# easyeda.net
KiCad netlist of a schematic drawn in EasyEDA Pro
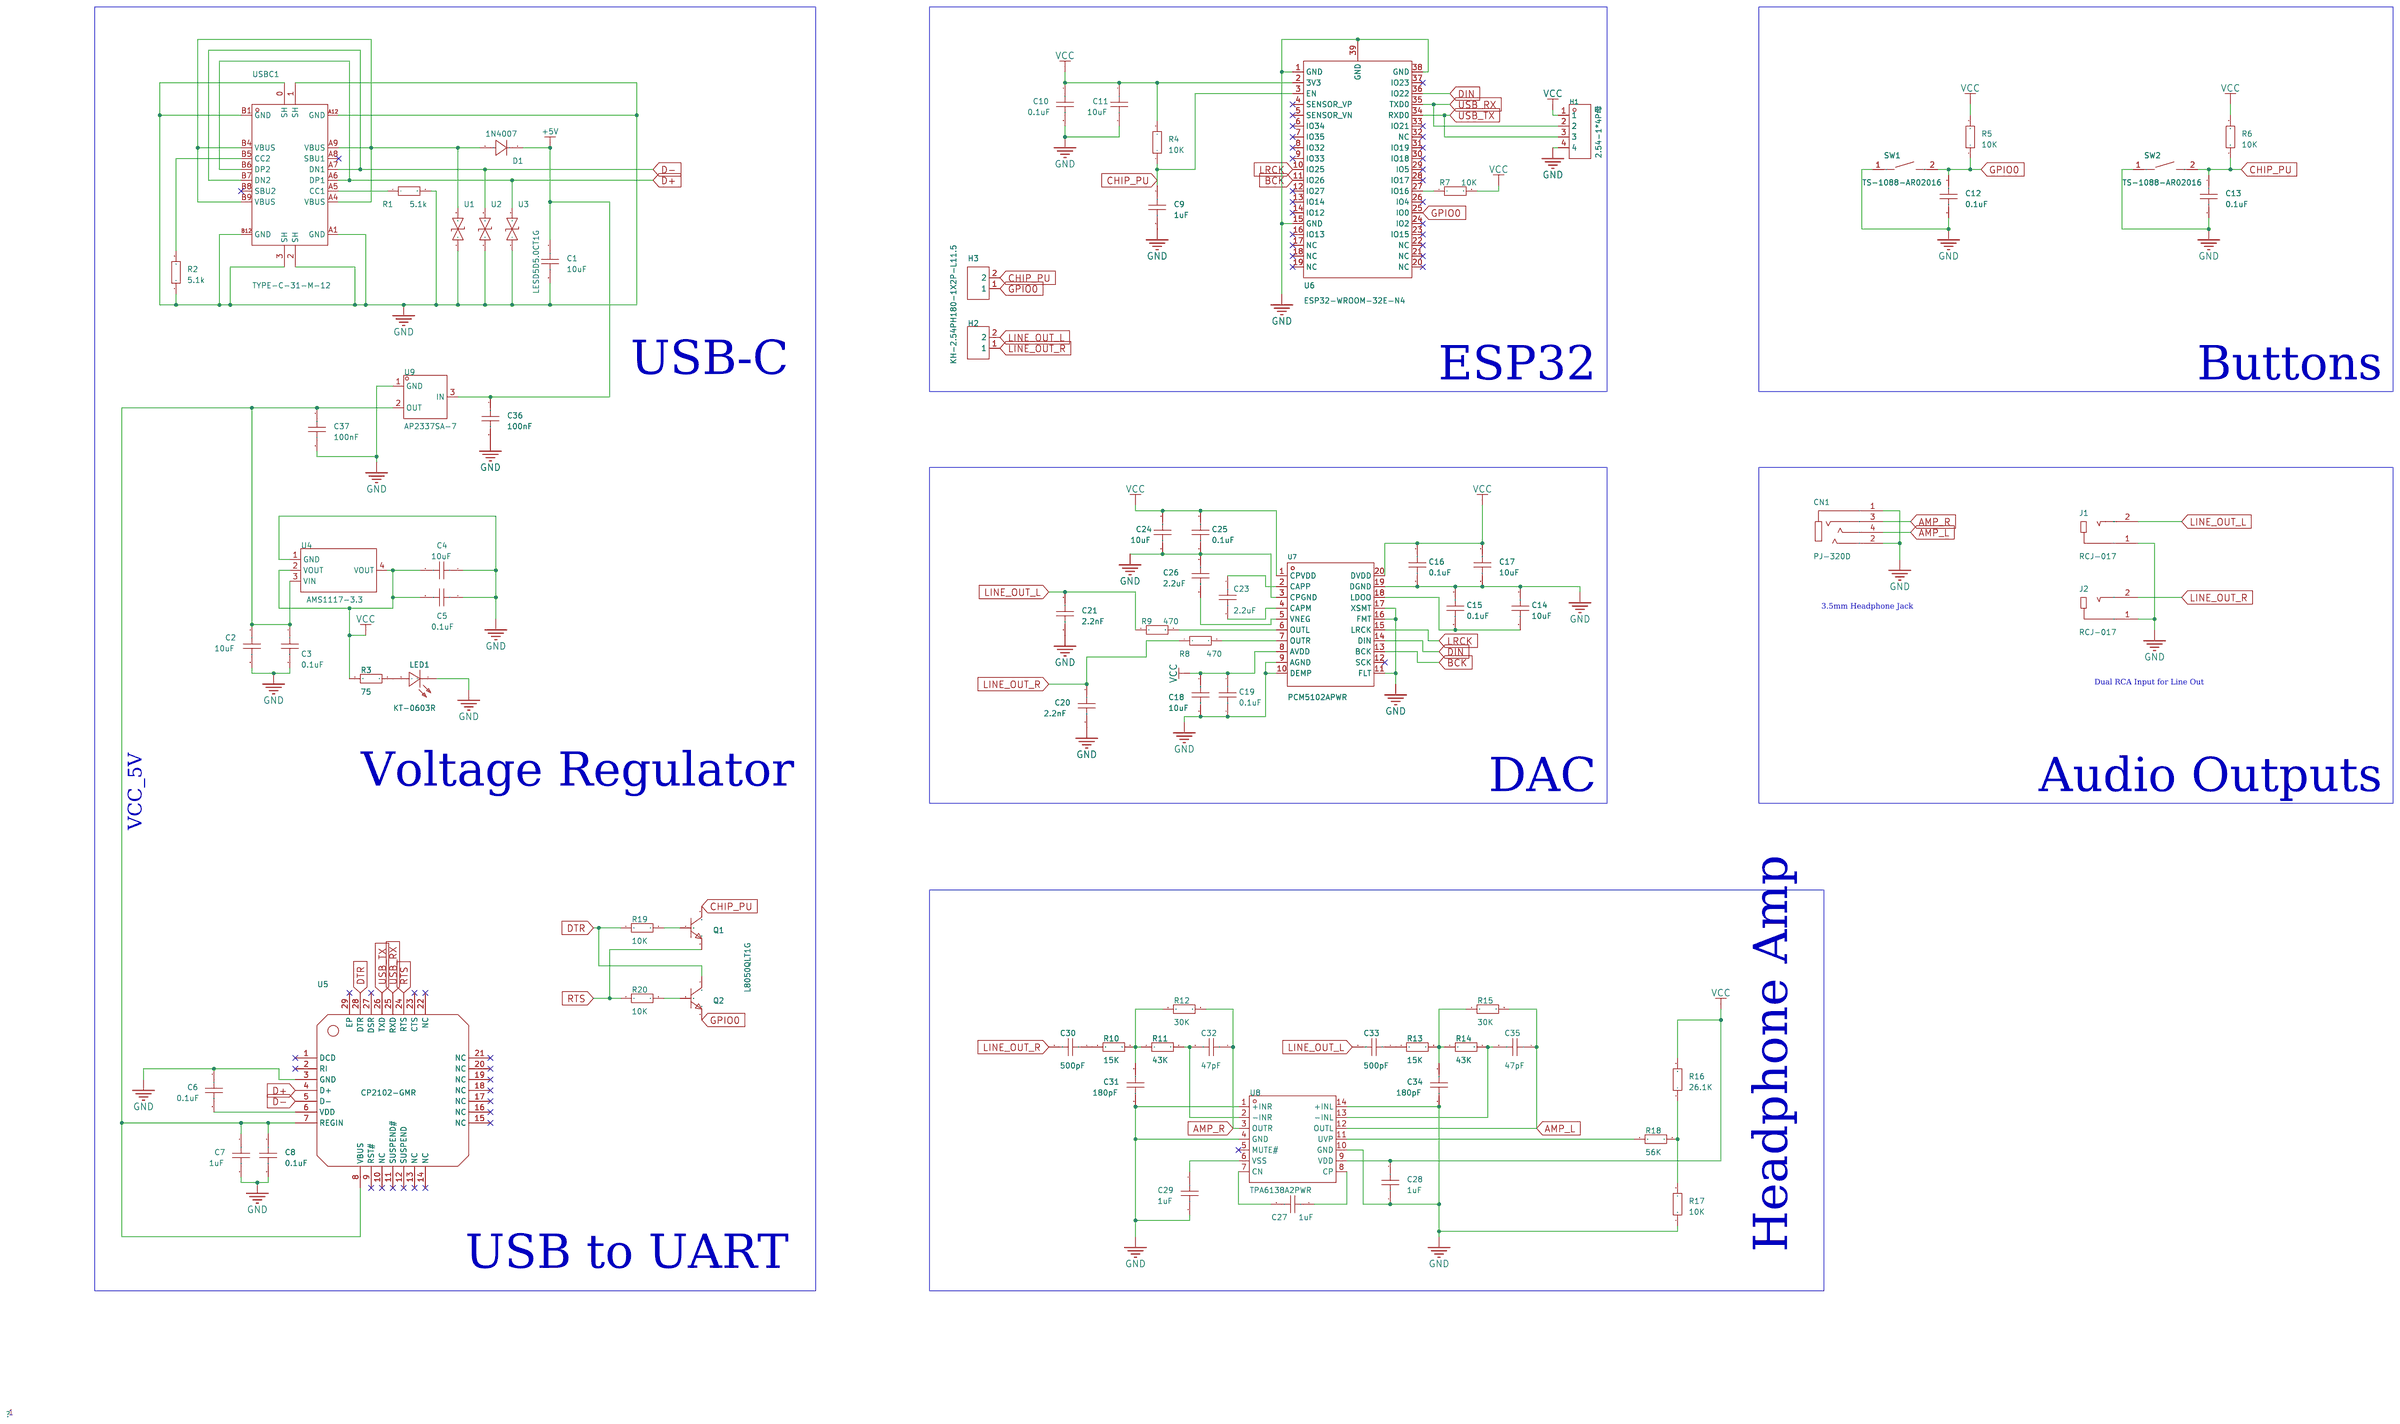
[diagram p0: schematic sheet]

(export (version "E")
  (design (tool "Eeschema 10.0.6"))
  (components
    (comp (ref "C1")
      (value "10uF")
      (footprint "easyedapro:C0603")
      (libsource (lib "easyedapro") (part "CAP"))
    )
    (comp (ref "C2")
      (value "10uF")
      (footprint "easyedapro:C0603")
      (libsource (lib "easyedapro") (part "CAP"))
    )
    (comp (ref "C3")
      (value "0.1uF")
      (footprint "easyedapro:C0603")
      (libsource (lib "easyedapro") (part "CAP"))
    )
    (comp (ref "C4")
      (value "10uF")
      (footprint "easyedapro:C0603")
      (libsource (lib "easyedapro") (part "CAP"))
    )
    (comp (ref "C5")
      (value "0.1uF")
      (footprint "easyedapro:C0603")
      (libsource (lib "easyedapro") (part "CAP"))
    )
    (comp (ref "C6")
      (value "0.1uF")
      (footprint "easyedapro:C0603")
      (libsource (lib "easyedapro") (part "CAP"))
    )
    (comp (ref "C7") (value "1uF") (footprint "easyedapro:C0603") (libsource (lib "easyedapro") (part "CAP")))
    (comp (ref "C8")
      (value "0.1uF")
      (footprint "easyedapro:C0603")
      (libsource (lib "easyedapro") (part "CAP"))
    )
    (comp (ref "C9") (value "1uF") (footprint "easyedapro:C0603") (libsource (lib "easyedapro") (part "CAP")))
    (comp (ref "C10")
      (value "0.1uF")
      (footprint "easyedapro:C0603")
      (libsource (lib "easyedapro") (part "CAP"))
    )
    (comp (ref "C11")
      (value "10uF")
      (footprint "easyedapro:C0603")
      (libsource (lib "easyedapro") (part "CAP"))
    )
    (comp (ref "C12")
      (value "0.1uF")
      (footprint "easyedapro:C0603")
      (libsource (lib "easyedapro") (part "CAP"))
    )
    (comp (ref "C13")
      (value "0.1uF")
      (footprint "easyedapro:C0603")
      (libsource (lib "easyedapro") (part "CAP"))
    )
    (comp (ref "C14")
      (value "10uF")
      (footprint "easyedapro:C0603")
      (libsource (lib "easyedapro") (part "CAP"))
    )
    (comp (ref "C15")
      (value "0.1uF")
      (footprint "easyedapro:C0603")
      (libsource (lib "easyedapro") (part "CAP"))
    )
    (comp (ref "C16")
      (value "0.1uF")
      (footprint "easyedapro:C0603")
      (libsource (lib "easyedapro") (part "CAP"))
    )
    (comp (ref "C17")
      (value "10uF")
      (footprint "easyedapro:C0603")
      (libsource (lib "easyedapro") (part "CAP"))
    )
    (comp (ref "C18")
      (value "10uF")
      (footprint "easyedapro:C0603")
      (libsource (lib "easyedapro") (part "CAP"))
    )
    (comp (ref "C19")
      (value "0.1uF")
      (footprint "easyedapro:C0603")
      (libsource (lib "easyedapro") (part "CAP"))
    )
    (comp (ref "C20")
      (value "2.2nF")
      (footprint "easyedapro:C0603")
      (libsource (lib "easyedapro") (part "CAP"))
    )
    (comp (ref "C21")
      (value "2.2nF")
      (footprint "easyedapro:C0603")
      (libsource (lib "easyedapro") (part "CAP"))
    )
    (comp (ref "C23")
      (value "2.2uF")
      (footprint "easyedapro:C0603")
      (libsource (lib "easyedapro") (part "CAP"))
    )
    (comp (ref "C24")
      (value "10uF")
      (footprint "easyedapro:C0603")
      (libsource (lib "easyedapro") (part "CAP"))
    )
    (comp (ref "C25")
      (value "0.1uF")
      (footprint "easyedapro:C0603")
      (libsource (lib "easyedapro") (part "CAP"))
    )
    (comp (ref "C26")
      (value "2.2uF")
      (footprint "easyedapro:C0603")
      (libsource (lib "easyedapro") (part "CAP"))
    )
    (comp (ref "C27")
      (value "1uF")
      (footprint "easyedapro:C0603")
      (libsource (lib "easyedapro") (part "CAP"))
    )
    (comp (ref "C28")
      (value "1uF")
      (footprint "easyedapro:C0603")
      (libsource (lib "easyedapro") (part "CAP"))
    )
    (comp (ref "C29")
      (value "1uF")
      (footprint "easyedapro:C0603")
      (libsource (lib "easyedapro") (part "CAP"))
    )
    (comp (ref "C30")
      (value "500pF")
      (footprint "easyedapro:C0603")
      (libsource (lib "easyedapro") (part "CAP"))
    )
    (comp (ref "C31")
      (value "180pF")
      (footprint "easyedapro:C0603")
      (libsource (lib "easyedapro") (part "CAP"))
    )
    (comp (ref "C32")
      (value "47pF")
      (footprint "easyedapro:C0603")
      (libsource (lib "easyedapro") (part "CAP"))
    )
    (comp (ref "C33")
      (value "500pF")
      (footprint "easyedapro:C0603")
      (libsource (lib "easyedapro") (part "CAP"))
    )
    (comp (ref "C34")
      (value "180pF")
      (footprint "easyedapro:C0603")
      (libsource (lib "easyedapro") (part "CAP"))
    )
    (comp (ref "C35")
      (value "47pF")
      (footprint "easyedapro:C0603")
      (libsource (lib "easyedapro") (part "CAP"))
    )
    (comp (ref "C36")
      (value "100nF")
      (footprint "easyedapro:C0603")
      (libsource (lib "easyedapro") (part "CAP"))
    )
    (comp (ref "C37")
      (value "100nF")
      (footprint "easyedapro:C0603")
      (libsource (lib "easyedapro") (part "CAP"))
    )
    (comp (ref "CN1")
      (value "PJ-320D")
      (footprint "easyedapro:AUDIO-SMD_PJ-320D")
      (fields (field (name "Manufacturer") "USAKRO(美韩)"))
      (libsource (lib "easyedapro") (part "PJ-320D_C521460"))
    )
    (comp (ref "D1")
      (value "1N4007")
      (footprint "easyedapro:SMA_L4.3-W2.5-LS5.0-RD")
      (fields (field (name "Manufacturer") "TWGMC(台湾迪嘉)"))
      (libsource (lib "easyedapro") (part "1N4007_C727081"))
    )
    (comp (ref "H1")
      (value "2.54-1*4P母")
      (footprint "easyedapro:HDR-TH_4P-P2.54-V-F")
      (fields (field (name "Manufacturer") "BOOMELE(博穆精密)"))
      (libsource (lib "easyedapro") (part "2.54-1*4P母"))
    )
    (comp (ref "H2")
      (value "KH-2.54PH180-1X2P-L11.5")
      (footprint "easyedapro:HDR-TH_2P-P2.54-V-M")
      (fields (field (name "Manufacturer") "kinghelm(金航标)"))
      (libsource (lib "easyedapro") (part "KH-2.54PH180-1X2P-L11.5"))
    )
    (comp (ref "H3")
      (value "KH-2.54PH180-1X2P-L11.5")
      (footprint "easyedapro:HDR-TH_2P-P2.54-V-M")
      (fields (field (name "Manufacturer") "kinghelm(金航标)"))
      (libsource (lib "easyedapro") (part "KH-2.54PH180-1X2P-L11.5"))
    )
    (comp (ref "J1")
      (value "RCJ-017")
      (footprint "easyedapro:CONN-TH_RCJ-013")
      (fields (field (name "Manufacturer") "CUI"))
      (libsource (lib "easyedapro") (part "RCJ-017"))
    )
    (comp (ref "J2")
      (value "RCJ-017")
      (footprint "easyedapro:CONN-TH_RCJ-013")
      (fields (field (name "Manufacturer") "CUI"))
      (libsource (lib "easyedapro") (part "RCJ-017"))
    )
    (comp (ref "LED1")
      (value "KT-0603R")
      (footprint "easyedapro:LED0603-RD")
      (fields (field (name "Manufacturer") "KENTO"))
      (libsource (lib "easyedapro") (part "KT-0603R"))
    )
    (comp (ref "Q1")
      (value "L8050QLT1G")
      (footprint "easyedapro:SOT-23-3_L2.9-W1.3-P1.90-LS2.4-BR")
      (fields (field (name "Manufacturer") "LRC(乐山无线电)"))
      (libsource (lib "easyedapro") (part "L8050QLT1G"))
    )
    (comp (ref "Q2")
      (value "L8050QLT1G")
      (footprint "easyedapro:SOT-23-3_L2.9-W1.3-P1.90-LS2.4-BR")
      (fields (field (name "Manufacturer") "LRC(乐山无线电)"))
      (libsource (lib "easyedapro") (part "L8050QLT1G"))
    )
    (comp (ref "R1")
      (value "5.1k")
      (footprint "easyedapro:R0603")
      (libsource (lib "easyedapro") (part "Res"))
    )
    (comp (ref "R2")
      (value "5.1k")
      (footprint "easyedapro:R0603")
      (libsource (lib "easyedapro") (part "Res"))
    )
    (comp (ref "R3") (value "75") (footprint "easyedapro:R0603") (libsource (lib "easyedapro") (part "Res")))
    (comp (ref "R4") (value "10K") (footprint "easyedapro:R0603") (libsource (lib "easyedapro") (part "Res")))
    (comp (ref "R5") (value "10K") (footprint "easyedapro:R0603") (libsource (lib "easyedapro") (part "Res")))
    (comp (ref "R6") (value "10K") (footprint "easyedapro:R0603") (libsource (lib "easyedapro") (part "Res")))
    (comp (ref "R7") (value "10K") (footprint "easyedapro:R0603") (libsource (lib "easyedapro") (part "Res")))
    (comp (ref "R8") (value "470") (footprint "easyedapro:R0603") (libsource (lib "easyedapro") (part "Res")))
    (comp (ref "R9") (value "470") (footprint "easyedapro:R0603") (libsource (lib "easyedapro") (part "Res")))
    (comp (ref "R10")
      (value "15K")
      (footprint "easyedapro:R0603")
      (libsource (lib "easyedapro") (part "Res"))
    )
    (comp (ref "R11")
      (value "43K")
      (footprint "easyedapro:R0603")
      (libsource (lib "easyedapro") (part "Res"))
    )
    (comp (ref "R12")
      (value "30K")
      (footprint "easyedapro:R0603")
      (libsource (lib "easyedapro") (part "Res"))
    )
    (comp (ref "R13")
      (value "15K")
      (footprint "easyedapro:R0603")
      (libsource (lib "easyedapro") (part "Res"))
    )
    (comp (ref "R14")
      (value "43K")
      (footprint "easyedapro:R0603")
      (libsource (lib "easyedapro") (part "Res"))
    )
    (comp (ref "R15")
      (value "30K")
      (footprint "easyedapro:R0603")
      (libsource (lib "easyedapro") (part "Res"))
    )
    (comp (ref "R16")
      (value "26.1K")
      (footprint "easyedapro:R0603")
      (libsource (lib "easyedapro") (part "Res"))
    )
    (comp (ref "R17")
      (value "10K")
      (footprint "easyedapro:R0603")
      (libsource (lib "easyedapro") (part "Res"))
    )
    (comp (ref "R18")
      (value "56K")
      (footprint "easyedapro:R0603")
      (libsource (lib "easyedapro") (part "Res"))
    )
    (comp (ref "R19")
      (value "10K")
      (footprint "easyedapro:R0603")
      (libsource (lib "easyedapro") (part "Res"))
    )
    (comp (ref "R20")
      (value "10K")
      (footprint "easyedapro:R0603")
      (libsource (lib "easyedapro") (part "Res"))
    )
    (comp (ref "SW1")
      (value "TS-1088-AR02016")
      (footprint "easyedapro:SW-SMD_L3.9-W3.0-P4.45")
      (fields (field (name "Manufacturer") "XUNPU(讯普)"))
      (libsource (lib "easyedapro") (part "TS-1088-AR02016"))
    )
    (comp (ref "SW2")
      (value "TS-1088-AR02016")
      (footprint "easyedapro:SW-SMD_L3.9-W3.0-P4.45")
      (fields (field (name "Manufacturer") "XUNPU(讯普)"))
      (libsource (lib "easyedapro") (part "TS-1088-AR02016"))
    )
    (comp (ref "U1")
      (value "LESD5D5.0CT1G")
      (footprint "easyedapro:SOD-523_L1.2-W0.8-LS1.6-BI")
      (fields (field (name "Manufacturer") "Leiditech(雷卯电子)"))
      (libsource (lib "easyedapro") (part "LESD5D5.0CT1G_C5246195"))
    )
    (comp (ref "U2")
      (value "LESD5D5.0CT1G")
      (footprint "easyedapro:SOD-523_L1.2-W0.8-LS1.6-BI")
      (fields (field (name "Manufacturer") "Leiditech(雷卯电子)"))
      (libsource (lib "easyedapro") (part "LESD5D5.0CT1G_C5246195"))
    )
    (comp (ref "U3")
      (value "LESD5D5.0CT1G")
      (footprint "easyedapro:SOD-523_L1.2-W0.8-LS1.6-BI")
      (fields (field (name "Manufacturer") "Leiditech(雷卯电子)"))
      (libsource (lib "easyedapro") (part "LESD5D5.0CT1G_C5246195"))
    )
    (comp (ref "U4")
      (value "AMS1117-3.3")
      (footprint "easyedapro:SOT-223-3_L6.5-W3.4-P2.30-LS7.0-BR")
      (fields (field (name "Manufacturer") "AMS"))
      (libsource (lib "easyedapro") (part "AMS1117-3.3"))
    )
    (comp (ref "U5")
      (value "CP2102-GMR")
      (footprint "easyedapro:WQFN-28_L5.0-W5.0-P0.50-BL-EP3.2")
      (fields (field (name "Manufacturer") "SKYWORKS/SILICON LABS(芯科)"))
      (libsource (lib "easyedapro") (part "CP2102-GMR"))
    )
    (comp (ref "U6")
      (value "ESP32-WROOM-32E-N4")
      (footprint "easyedapro:WIFI-SMD_ESP32-WROOM-32E")
      (fields (field (name "Manufacturer") "ESPRESSIF(乐鑫)"))
      (libsource (lib "easyedapro") (part "ESP32-WROOM-32E(4MB)"))
    )
    (comp (ref "U7")
      (value "PCM5102APWR")
      (footprint "easyedapro:TSSOP-20_L6.5-W4.4-P0.65-LS6.4-BL")
      (fields (field (name "Manufacturer") "TI(德州仪器)"))
      (libsource (lib "easyedapro") (part "PCM5102APWR"))
    )
    (comp (ref "U8")
      (value "TPA6138A2PWR")
      (footprint "easyedapro:TSSOP-14_L5.0-W4.4-P0.65-LS6.4-BL")
      (fields (field (name "Manufacturer") "TI(德州仪器)"))
      (libsource (lib "easyedapro") (part "TPA6138A2PWR"))
    )
    (comp (ref "U9")
      (value "AP2337SA-7")
      (footprint "easyedapro:SOT-23-3_L2.9-W1.3-P1.90-LS2.4-BR")
      (fields (field (name "Manufacturer") "DIODES(美台)"))
      (libsource (lib "easyedapro") (part "AP2337SA-7"))
    )
    (comp (ref "USBC1")
      (value "TYPE-C-31-M-12")
      (footprint "easyedapro:USB-C_SMD-TYPE-C-31-M-12")
      (fields (field (name "Manufacturer") "韩国韩荣"))
      (libsource (lib "easyedapro") (part "TYPE-C-31-M-12"))
    )
  )
  (nets
    (net (code "1") (name "+5V") (class "Default")
      (node (ref "C1") (pin "1") (pinfunction "1_1") (pintype "input"))
      (node (ref "C36") (pin "1") (pinfunction "1_1") (pintype "input"))
      (node (ref "D1") (pin "1") (pinfunction "K_1") (pintype "unspecified"))
      (node (ref "U9") (pin "3") (pinfunction "IN_3") (pintype "input"))
    )
    (net (code "2") (name "AMP_L") (class "Default")
      (node (ref "C35") (pin "1") (pinfunction "1_1") (pintype "input"))
      (node (ref "CN1") (pin "4") (pinfunction "4_4") (pintype "input"))
      (node (ref "R15") (pin "2") (pinfunction "2_2") (pintype "input"))
      (node (ref "U8") (pin "12") (pinfunction "OUTL_12") (pintype "unspecified"))
    )
    (net (code "3") (name "AMP_R") (class "Default")
      (node (ref "C32") (pin "1") (pinfunction "1_1") (pintype "input"))
      (node (ref "CN1") (pin "3") (pinfunction "3_3") (pintype "input"))
      (node (ref "R12") (pin "2") (pinfunction "2_2") (pintype "input"))
      (node (ref "U8") (pin "3") (pinfunction "OUTR_3") (pintype "unspecified"))
    )
    (net (code "4") (name "BCK") (class "Default")
      (node (ref "U6") (pin "11") (pinfunction "IO26_11") (pintype "unspecified"))
      (node (ref "U7") (pin "13") (pinfunction "BCK_13") (pintype "input"))
    )
    (net (code "5") (name "CHIP_PU") (class "Default")
      (node (ref "C13") (pin "1") (pinfunction "1_1") (pintype "input"))
      (node (ref "C9") (pin "1") (pinfunction "1_1") (pintype "input"))
      (node (ref "H3") (pin "2") (pinfunction "2_2") (pintype "unspecified"))
      (node (ref "Q1") (pin "3") (pinfunction "C_3") (pintype "unspecified"))
      (node (ref "R4") (pin "1") (pinfunction "1_1") (pintype "input"))
      (node (ref "R6") (pin "1") (pinfunction "1_1") (pintype "input"))
      (node (ref "SW2") (pin "2") (pinfunction "2_2") (pintype "unspecified"))
      (node (ref "U6") (pin "3") (pinfunction "EN_3") (pintype "unspecified"))
    )
    (net (code "6") (name "D+") (class "Default")
      (node (ref "U3") (pin "2") (pinfunction "2_2") (pintype "unspecified"))
      (node (ref "U5") (pin "4") (pinfunction "D+_4") (pintype "unspecified"))
      (node (ref "USBC1") (pin "A6") (pinfunction "DP1_A6") (pintype "unspecified"))
      (node (ref "USBC1") (pin "B6") (pinfunction "DP2_B6") (pintype "unspecified"))
    )
    (net (code "7") (name "D-") (class "Default")
      (node (ref "U2") (pin "2") (pinfunction "2_2") (pintype "unspecified"))
      (node (ref "U5") (pin "5") (pinfunction "D-_5") (pintype "unspecified"))
      (node (ref "USBC1") (pin "A7") (pinfunction "DN1_A7") (pintype "unspecified"))
      (node (ref "USBC1") (pin "B7") (pinfunction "DN2_B7") (pintype "unspecified"))
    )
    (net (code "8") (name "DIN") (class "Default")
      (node (ref "U6") (pin "36") (pinfunction "IO22_36") (pintype "unspecified"))
      (node (ref "U7") (pin "14") (pinfunction "DIN_14") (pintype "input"))
    )
    (net (code "9") (name "DTR") (class "Default")
      (node (ref "Q2") (pin "3") (pinfunction "C_3") (pintype "unspecified"))
      (node (ref "R19") (pin "1") (pinfunction "1_1") (pintype "input"))
      (node (ref "U5") (pin "28") (pinfunction "DTR_28") (pintype "unspecified"))
    )
    (net (code "10") (name "GND") (class "Default")
      (node (ref "C1") (pin "2") (pinfunction "2_2") (pintype "input"))
      (node (ref "C10") (pin "2") (pinfunction "2_2") (pintype "input"))
      (node (ref "C11") (pin "2") (pinfunction "2_2") (pintype "input"))
      (node (ref "C12") (pin "2") (pinfunction "2_2") (pintype "input"))
      (node (ref "C13") (pin "2") (pinfunction "2_2") (pintype "input"))
      (node (ref "C14") (pin "1") (pinfunction "1_1") (pintype "input"))
      (node (ref "C15") (pin "1") (pinfunction "1_1") (pintype "input"))
      (node (ref "C16") (pin "2") (pinfunction "2_2") (pintype "input"))
      (node (ref "C17") (pin "2") (pinfunction "2_2") (pintype "input"))
      (node (ref "C18") (pin "2") (pinfunction "2_2") (pintype "input"))
      (node (ref "C19") (pin "2") (pinfunction "2_2") (pintype "input"))
      (node (ref "C2") (pin "2") (pinfunction "2_2") (pintype "input"))
      (node (ref "C20") (pin "2") (pinfunction "2_2") (pintype "input"))
      (node (ref "C21") (pin "2") (pinfunction "2_2") (pintype "input"))
      (node (ref "C24") (pin "2") (pinfunction "2_2") (pintype "input"))
      (node (ref "C25") (pin "2") (pinfunction "2_2") (pintype "input"))
      (node (ref "C26") (pin "1") (pinfunction "1_1") (pintype "input"))
      (node (ref "C28") (pin "2") (pinfunction "2_2") (pintype "input"))
      (node (ref "C29") (pin "2") (pinfunction "2_2") (pintype "input"))
      (node (ref "C3") (pin "2") (pinfunction "2_2") (pintype "input"))
      (node (ref "C31") (pin "2") (pinfunction "2_2") (pintype "input"))
      (node (ref "C34") (pin "2") (pinfunction "2_2") (pintype "input"))
      (node (ref "C36") (pin "2") (pinfunction "2_2") (pintype "input"))
      (node (ref "C37") (pin "2") (pinfunction "2_2") (pintype "input"))
      (node (ref "C4") (pin "1") (pinfunction "1_1") (pintype "input"))
      (node (ref "C5") (pin "1") (pinfunction "1_1") (pintype "input"))
      (node (ref "C6") (pin "1") (pinfunction "1_1") (pintype "input"))
      (node (ref "C7") (pin "2") (pinfunction "2_2") (pintype "input"))
      (node (ref "C8") (pin "2") (pinfunction "2_2") (pintype "input"))
      (node (ref "C9") (pin "2") (pinfunction "2_2") (pintype "input"))
      (node (ref "CN1") (pin "1") (pinfunction "1_1") (pintype "input"))
      (node (ref "CN1") (pin "2") (pinfunction "2_2") (pintype "input"))
      (node (ref "H1") (pin "4") (pinfunction "4_4") (pintype "input"))
      (node (ref "J1") (pin "1") (pinfunction "1_1") (pintype "unspecified"))
      (node (ref "J2") (pin "1") (pinfunction "1_1") (pintype "unspecified"))
      (node (ref "LED1") (pin "1") (pinfunction "K_1") (pintype "unspecified"))
      (node (ref "R1") (pin "2") (pinfunction "2_2") (pintype "input"))
      (node (ref "R17") (pin "1") (pinfunction "1_1") (pintype "input"))
      (node (ref "R2") (pin "1") (pinfunction "1_1") (pintype "input"))
      (node (ref "SW1") (pin "1") (pinfunction "1_1") (pintype "unspecified"))
      (node (ref "SW2") (pin "1") (pinfunction "1_1") (pintype "unspecified"))
      (node (ref "U1") (pin "1") (pinfunction "1_1") (pintype "unspecified"))
      (node (ref "U2") (pin "1") (pinfunction "1_1") (pintype "unspecified"))
      (node (ref "U3") (pin "1") (pinfunction "1_1") (pintype "unspecified"))
      (node (ref "U4") (pin "1") (pinfunction "GND_1") (pintype "unspecified"))
      (node (ref "U5") (pin "3") (pinfunction "GND_3") (pintype "unspecified"))
      (node (ref "U6") (pin "1") (pinfunction "GND_1") (pintype "unspecified"))
      (node (ref "U6") (pin "15") (pinfunction "GND_15") (pintype "unspecified"))
      (node (ref "U6") (pin "38") (pinfunction "GND_38") (pintype "unspecified"))
      (node (ref "U6") (pin "39") (pinfunction "GND_39") (pintype "unspecified"))
      (node (ref "U7") (pin "10") (pinfunction "DEMP_10") (pintype "input"))
      (node (ref "U7") (pin "11") (pinfunction "FLT_11") (pintype "input"))
      (node (ref "U7") (pin "16") (pinfunction "FMT_16") (pintype "input"))
      (node (ref "U7") (pin "17") (pinfunction "XSMT_17") (pintype "input"))
      (node (ref "U7") (pin "19") (pinfunction "DGND_19") (pintype "input"))
      (node (ref "U7") (pin "3") (pinfunction "CPGND_3") (pintype "input"))
      (node (ref "U7") (pin "9") (pinfunction "AGND_9") (pintype "input"))
      (node (ref "U8") (pin "1") (pinfunction "+INR_1") (pintype "unspecified"))
      (node (ref "U8") (pin "10") (pinfunction "GND_10") (pintype "unspecified"))
      (node (ref "U8") (pin "14") (pinfunction "+INL_14") (pintype "unspecified"))
      (node (ref "U8") (pin "4") (pinfunction "GND_4") (pintype "unspecified"))
      (node (ref "U9") (pin "1") (pinfunction "GND_1") (pintype "input"))
      (node (ref "USBC1") (pin "0") (pinfunction "SH_0") (pintype "unspecified"))
      (node (ref "USBC1") (pin "1") (pinfunction "SH_1") (pintype "unspecified"))
      (node (ref "USBC1") (pin "2") (pinfunction "SH_2") (pintype "unspecified"))
      (node (ref "USBC1") (pin "3") (pinfunction "SH_3") (pintype "unspecified"))
      (node (ref "USBC1") (pin "A1") (pinfunction "GND_A1") (pintype "unspecified"))
      (node (ref "USBC1") (pin "A12") (pinfunction "GND_A12") (pintype "unspecified"))
      (node (ref "USBC1") (pin "B1") (pinfunction "GND_B1") (pintype "unspecified"))
      (node (ref "USBC1") (pin "B12") (pinfunction "GND_B12") (pintype "unspecified"))
    )
    (net (code "11") (name "GPIO0") (class "Default")
      (node (ref "C12") (pin "1") (pinfunction "1_1") (pintype "input"))
      (node (ref "H3") (pin "1") (pinfunction "1_1") (pintype "unspecified"))
      (node (ref "Q2") (pin "2") (pinfunction "E_2") (pintype "unspecified"))
      (node (ref "R5") (pin "1") (pinfunction "1_1") (pintype "input"))
      (node (ref "SW1") (pin "2") (pinfunction "2_2") (pintype "unspecified"))
      (node (ref "U6") (pin "25") (pinfunction "IO0_25") (pintype "unspecified"))
    )
    (net (code "12") (name "LINE_OUT_L") (class "Default")
      (node (ref "C21") (pin "1") (pinfunction "1_1") (pintype "input"))
      (node (ref "C33") (pin "2") (pinfunction "2_2") (pintype "input"))
      (node (ref "H2") (pin "2") (pinfunction "2_2") (pintype "unspecified"))
      (node (ref "J1") (pin "2") (pinfunction "2_2") (pintype "unspecified"))
      (node (ref "R9") (pin "1") (pinfunction "1_1") (pintype "input"))
    )
    (net (code "13") (name "LINE_OUT_R") (class "Default")
      (node (ref "C20") (pin "1") (pinfunction "1_1") (pintype "input"))
      (node (ref "C30") (pin "2") (pinfunction "2_2") (pintype "input"))
      (node (ref "H2") (pin "1") (pinfunction "1_1") (pintype "unspecified"))
      (node (ref "J2") (pin "2") (pinfunction "2_2") (pintype "unspecified"))
      (node (ref "R8") (pin "1") (pinfunction "1_1") (pintype "input"))
    )
    (net (code "14") (name "LRCK") (class "Default")
      (node (ref "U6") (pin "10") (pinfunction "IO25_10") (pintype "unspecified"))
      (node (ref "U7") (pin "15") (pinfunction "LRCK_15") (pintype "input"))
    )
    (net (code "15") (name "Net-(C30-Pad1)") (class "Default")
      (node (ref "C30") (pin "1") (pinfunction "1_1") (pintype "input"))
      (node (ref "R10") (pin "1") (pinfunction "1_1") (pintype "input"))
    )
    (net (code "16") (name "Net-(C31-Pad1)") (class "Default")
      (node (ref "C31") (pin "1") (pinfunction "1_1") (pintype "input"))
      (node (ref "R10") (pin "2") (pinfunction "2_2") (pintype "input"))
      (node (ref "R11") (pin "1") (pinfunction "1_1") (pintype "input"))
      (node (ref "R12") (pin "1") (pinfunction "1_1") (pintype "input"))
    )
    (net (code "17") (name "Net-(C33-Pad1)") (class "Default")
      (node (ref "C33") (pin "1") (pinfunction "1_1") (pintype "input"))
      (node (ref "R13") (pin "1") (pinfunction "1_1") (pintype "input"))
    )
    (net (code "18") (name "Net-(C34-Pad1)") (class "Default")
      (node (ref "C34") (pin "1") (pinfunction "1_1") (pintype "input"))
      (node (ref "R13") (pin "2") (pinfunction "2_2") (pintype "input"))
      (node (ref "R14") (pin "1") (pinfunction "1_1") (pintype "input"))
      (node (ref "R15") (pin "1") (pinfunction "1_1") (pintype "input"))
    )
    (net (code "19") (name "Net-(D1-A)") (class "Default")
      (node (ref "D1") (pin "2") (pinfunction "A_2") (pintype "unspecified"))
      (node (ref "U1") (pin "2") (pinfunction "2_2") (pintype "unspecified"))
      (node (ref "USBC1") (pin "A4") (pinfunction "VBUS_A4") (pintype "unspecified"))
      (node (ref "USBC1") (pin "A9") (pinfunction "VBUS_A9") (pintype "unspecified"))
      (node (ref "USBC1") (pin "B4") (pinfunction "VBUS_B4") (pintype "unspecified"))
      (node (ref "USBC1") (pin "B9") (pinfunction "VBUS_B9") (pintype "unspecified"))
    )
    (net (code "20") (name "Net-(LED1-A)") (class "Default")
      (node (ref "LED1") (pin "2") (pinfunction "A_2") (pintype "unspecified"))
      (node (ref "R3") (pin "1") (pinfunction "1_1") (pintype "input"))
    )
    (net (code "21") (name "Net-(Q1-B)") (class "Default")
      (node (ref "Q1") (pin "1") (pinfunction "B_1") (pintype "unspecified"))
      (node (ref "R19") (pin "2") (pinfunction "2_2") (pintype "input"))
    )
    (net (code "22") (name "Net-(Q2-B)") (class "Default")
      (node (ref "Q2") (pin "1") (pinfunction "B_1") (pintype "unspecified"))
      (node (ref "R20") (pin "2") (pinfunction "2_2") (pintype "input"))
    )
    (net (code "23") (name "Net-(R16-Pad1)") (class "Default")
      (node (ref "R16") (pin "1") (pinfunction "1_1") (pintype "input"))
      (node (ref "R17") (pin "2") (pinfunction "2_2") (pintype "input"))
      (node (ref "R18") (pin "2") (pinfunction "2_2") (pintype "input"))
    )
    (net (code "24") (name "Net-(U4-VIN)") (class "Default")
      (node (ref "C2") (pin "1") (pinfunction "1_1") (pintype "input"))
      (node (ref "C3") (pin "1") (pinfunction "1_1") (pintype "input"))
      (node (ref "C37") (pin "1") (pinfunction "1_1") (pintype "input"))
      (node (ref "C7") (pin "1") (pinfunction "1_1") (pintype "input"))
      (node (ref "C8") (pin "1") (pinfunction "1_1") (pintype "input"))
      (node (ref "U4") (pin "3") (pinfunction "VIN_3") (pintype "unspecified"))
      (node (ref "U5") (pin "7") (pinfunction "REGIN_7") (pintype "unspecified"))
      (node (ref "U5") (pin "8") (pinfunction "VBUS_8") (pintype "unspecified"))
      (node (ref "U9") (pin "2") (pinfunction "OUT_2") (pintype "input"))
    )
    (net (code "25") (name "Net-(U5-VDD)") (class "Default")
      (node (ref "C6") (pin "2") (pinfunction "2_2") (pintype "input"))
      (node (ref "U5") (pin "6") (pinfunction "VDD_6") (pintype "unspecified"))
    )
    (net (code "26") (name "Net-(U6-IO16)") (class "Default")
      (node (ref "R7") (pin "1") (pinfunction "1_1") (pintype "input"))
      (node (ref "U6") (pin "27") (pinfunction "IO16_27") (pintype "unspecified"))
    )
    (net (code "27") (name "Net-(U7-CAPM)") (class "Default")
      (node (ref "C23") (pin "2") (pinfunction "2_2") (pintype "input"))
      (node (ref "U7") (pin "4") (pinfunction "CAPM_4") (pintype "input"))
    )
    (net (code "28") (name "Net-(U7-CAPP)") (class "Default")
      (node (ref "C23") (pin "1") (pinfunction "1_1") (pintype "input"))
      (node (ref "U7") (pin "2") (pinfunction "CAPP_2") (pintype "input"))
    )
    (net (code "29") (name "Net-(U7-LDOO)") (class "Default")
      (node (ref "C14") (pin "2") (pinfunction "2_2") (pintype "input"))
      (node (ref "C15") (pin "2") (pinfunction "2_2") (pintype "input"))
      (node (ref "U7") (pin "18") (pinfunction "LDOO_18") (pintype "input"))
    )
    (net (code "30") (name "Net-(U7-OUTL)") (class "Default")
      (node (ref "R9") (pin "2") (pinfunction "2_2") (pintype "input"))
      (node (ref "U7") (pin "6") (pinfunction "OUTL_6") (pintype "input"))
    )
    (net (code "31") (name "Net-(U7-OUTR)") (class "Default")
      (node (ref "R8") (pin "2") (pinfunction "2_2") (pintype "input"))
      (node (ref "U7") (pin "7") (pinfunction "OUTR_7") (pintype "input"))
    )
    (net (code "32") (name "Net-(U7-VNEG)") (class "Default")
      (node (ref "C26") (pin "2") (pinfunction "2_2") (pintype "input"))
      (node (ref "U7") (pin "5") (pinfunction "VNEG_5") (pintype "input"))
    )
    (net (code "33") (name "Net-(U8--INL)") (class "Default")
      (node (ref "C35") (pin "2") (pinfunction "2_2") (pintype "input"))
      (node (ref "R14") (pin "2") (pinfunction "2_2") (pintype "input"))
      (node (ref "U8") (pin "13") (pinfunction "-INL_13") (pintype "unspecified"))
    )
    (net (code "34") (name "Net-(U8--INR)") (class "Default")
      (node (ref "C32") (pin "2") (pinfunction "2_2") (pintype "input"))
      (node (ref "R11") (pin "2") (pinfunction "2_2") (pintype "input"))
      (node (ref "U8") (pin "2") (pinfunction "-INR_2") (pintype "unspecified"))
    )
    (net (code "35") (name "Net-(U8-CN)") (class "Default")
      (node (ref "C27") (pin "2") (pinfunction "2_2") (pintype "input"))
      (node (ref "U8") (pin "7") (pinfunction "CN_7") (pintype "unspecified"))
    )
    (net (code "36") (name "Net-(U8-CP)") (class "Default")
      (node (ref "C27") (pin "1") (pinfunction "1_1") (pintype "input"))
      (node (ref "U8") (pin "8") (pinfunction "CP_8") (pintype "unspecified"))
    )
    (net (code "37") (name "Net-(U8-UVP)") (class "Default")
      (node (ref "R18") (pin "1") (pinfunction "1_1") (pintype "input"))
      (node (ref "U8") (pin "11") (pinfunction "UVP_11") (pintype "unspecified"))
    )
    (net (code "38") (name "Net-(U8-VSS)") (class "Default")
      (node (ref "C29") (pin "1") (pinfunction "1_1") (pintype "input"))
      (node (ref "U8") (pin "6") (pinfunction "VSS_6") (pintype "unspecified"))
    )
    (net (code "39") (name "Net-(USBC1-CC1)") (class "Default")
      (node (ref "R1") (pin "1") (pinfunction "1_1") (pintype "input"))
      (node (ref "USBC1") (pin "A5") (pinfunction "CC1_A5") (pintype "unspecified"))
    )
    (net (code "40") (name "Net-(USBC1-CC2)") (class "Default")
      (node (ref "R2") (pin "2") (pinfunction "2_2") (pintype "input"))
      (node (ref "USBC1") (pin "B5") (pinfunction "CC2_B5") (pintype "unspecified"))
    )
    (net (code "41") (name "RTS") (class "Default")
      (node (ref "Q1") (pin "2") (pinfunction "E_2") (pintype "unspecified"))
      (node (ref "R20") (pin "1") (pinfunction "1_1") (pintype "input"))
      (node (ref "U5") (pin "24") (pinfunction "RTS_24") (pintype "unspecified"))
    )
    (net (code "42") (name "USB_RX") (class "Default")
      (node (ref "H1") (pin "2") (pinfunction "2_2") (pintype "input"))
      (node (ref "U5") (pin "25") (pinfunction "RXD_25") (pintype "unspecified"))
      (node (ref "U6") (pin "35") (pinfunction "TXD0_35") (pintype "unspecified"))
    )
    (net (code "43") (name "USB_TX") (class "Default")
      (node (ref "H1") (pin "3") (pinfunction "3_3") (pintype "input"))
      (node (ref "U5") (pin "26") (pinfunction "TXD_26") (pintype "unspecified"))
      (node (ref "U6") (pin "34") (pinfunction "RXD0_34") (pintype "unspecified"))
    )
    (net (code "44") (name "VCC") (class "Default")
      (node (ref "C10") (pin "1") (pinfunction "1_1") (pintype "input"))
      (node (ref "C11") (pin "1") (pinfunction "1_1") (pintype "input"))
      (node (ref "C16") (pin "1") (pinfunction "1_1") (pintype "input"))
      (node (ref "C17") (pin "1") (pinfunction "1_1") (pintype "input"))
      (node (ref "C18") (pin "1") (pinfunction "1_1") (pintype "input"))
      (node (ref "C19") (pin "1") (pinfunction "1_1") (pintype "input"))
      (node (ref "C24") (pin "1") (pinfunction "1_1") (pintype "input"))
      (node (ref "C25") (pin "1") (pinfunction "1_1") (pintype "input"))
      (node (ref "C28") (pin "1") (pinfunction "1_1") (pintype "input"))
      (node (ref "C4") (pin "2") (pinfunction "2_2") (pintype "input"))
      (node (ref "C5") (pin "2") (pinfunction "2_2") (pintype "input"))
      (node (ref "H1") (pin "1") (pinfunction "1_1") (pintype "input"))
      (node (ref "R16") (pin "2") (pinfunction "2_2") (pintype "input"))
      (node (ref "R3") (pin "2") (pinfunction "2_2") (pintype "input"))
      (node (ref "R4") (pin "2") (pinfunction "2_2") (pintype "input"))
      (node (ref "R5") (pin "2") (pinfunction "2_2") (pintype "input"))
      (node (ref "R6") (pin "2") (pinfunction "2_2") (pintype "input"))
      (node (ref "R7") (pin "2") (pinfunction "2_2") (pintype "input"))
      (node (ref "U4") (pin "2") (pinfunction "VOUT_2") (pintype "unspecified"))
      (node (ref "U4") (pin "4") (pinfunction "VOUT_4") (pintype "unspecified"))
      (node (ref "U6") (pin "2") (pinfunction "3V3_2") (pintype "unspecified"))
      (node (ref "U7") (pin "1") (pinfunction "CPVDD_1") (pintype "input"))
      (node (ref "U7") (pin "20") (pinfunction "DVDD_20") (pintype "input"))
      (node (ref "U7") (pin "8") (pinfunction "AVDD_8") (pintype "input"))
      (node (ref "U8") (pin "9") (pinfunction "VDD_9") (pintype "unspecified"))
    )
    (net (code "45") (name "unconnected-(U5-CTS-Pad23)") (class "Default")
      (node (ref "U5") (pin "23") (pinfunction "CTS_23") (pintype "unspecified+no_connect"))
    )
    (net (code "46") (name "unconnected-(U5-DCD-Pad1)") (class "Default")
      (node (ref "U5") (pin "1") (pinfunction "DCD_1") (pintype "unspecified+no_connect"))
    )
    (net (code "47") (name "unconnected-(U5-DSR-Pad27)") (class "Default")
      (node (ref "U5") (pin "27") (pinfunction "DSR_27") (pintype "unspecified+no_connect"))
    )
    (net (code "48") (name "unconnected-(U5-EP-Pad29)") (class "Default")
      (node (ref "U5") (pin "29") (pinfunction "EP_29") (pintype "unspecified+no_connect"))
    )
    (net (code "49") (name "unconnected-(U5-NC-Pad10)") (class "Default")
      (node (ref "U5") (pin "10") (pinfunction "NC_10") (pintype "unspecified+no_connect"))
    )
    (net (code "50") (name "unconnected-(U5-NC-Pad13)") (class "Default")
      (node (ref "U5") (pin "13") (pinfunction "NC_13") (pintype "unspecified+no_connect"))
    )
    (net (code "51") (name "unconnected-(U5-NC-Pad14)") (class "Default")
      (node (ref "U5") (pin "14") (pinfunction "NC_14") (pintype "unspecified+no_connect"))
    )
    (net (code "52") (name "unconnected-(U5-NC-Pad15)") (class "Default")
      (node (ref "U5") (pin "15") (pinfunction "NC_15") (pintype "unspecified+no_connect"))
    )
    (net (code "53") (name "unconnected-(U5-NC-Pad16)") (class "Default")
      (node (ref "U5") (pin "16") (pinfunction "NC_16") (pintype "unspecified+no_connect"))
    )
    (net (code "54") (name "unconnected-(U5-NC-Pad17)") (class "Default")
      (node (ref "U5") (pin "17") (pinfunction "NC_17") (pintype "unspecified+no_connect"))
    )
    (net (code "55") (name "unconnected-(U5-NC-Pad18)") (class "Default")
      (node (ref "U5") (pin "18") (pinfunction "NC_18") (pintype "unspecified+no_connect"))
    )
    (net (code "56") (name "unconnected-(U5-NC-Pad19)") (class "Default")
      (node (ref "U5") (pin "19") (pinfunction "NC_19") (pintype "unspecified+no_connect"))
    )
    (net (code "57") (name "unconnected-(U5-NC-Pad20)") (class "Default")
      (node (ref "U5") (pin "20") (pinfunction "NC_20") (pintype "unspecified+no_connect"))
    )
    (net (code "58") (name "unconnected-(U5-NC-Pad21)") (class "Default")
      (node (ref "U5") (pin "21") (pinfunction "NC_21") (pintype "unspecified+no_connect"))
    )
    (net (code "59") (name "unconnected-(U5-NC-Pad22)") (class "Default")
      (node (ref "U5") (pin "22") (pinfunction "NC_22") (pintype "unspecified+no_connect"))
    )
    (net (code "60") (name "unconnected-(U5-RI-Pad2)") (class "Default")
      (node (ref "U5") (pin "2") (pinfunction "RI_2") (pintype "unspecified+no_connect"))
    )
    (net (code "61") (name "unconnected-(U5-RST#-Pad9)") (class "Default")
      (node (ref "U5") (pin "9") (pinfunction "RST#_9") (pintype "unspecified+no_connect"))
    )
    (net (code "62") (name "unconnected-(U5-SUSPEND#-Pad11)") (class "Default")
      (node (ref "U5") (pin "11") (pinfunction "SUSPEND#_11") (pintype "unspecified+no_connect"))
    )
    (net (code "63") (name "unconnected-(U5-SUSPEND-Pad12)") (class "Default")
      (node (ref "U5") (pin "12") (pinfunction "SUSPEND_12") (pintype "unspecified+no_connect"))
    )
    (net (code "64") (name "unconnected-(U6-IO2-Pad24)") (class "Default")
      (node (ref "U6") (pin "24") (pinfunction "IO2_24") (pintype "unspecified+no_connect"))
    )
    (net (code "65") (name "unconnected-(U6-IO4-Pad26)") (class "Default")
      (node (ref "U6") (pin "26") (pinfunction "IO4_26") (pintype "unspecified+no_connect"))
    )
    (net (code "66") (name "unconnected-(U6-IO5-Pad29)") (class "Default")
      (node (ref "U6") (pin "29") (pinfunction "IO5_29") (pintype "unspecified+no_connect"))
    )
    (net (code "67") (name "unconnected-(U6-IO12-Pad14)") (class "Default")
      (node (ref "U6") (pin "14") (pinfunction "IO12_14") (pintype "unspecified+no_connect"))
    )
    (net (code "68") (name "unconnected-(U6-IO13-Pad16)") (class "Default")
      (node (ref "U6") (pin "16") (pinfunction "IO13_16") (pintype "unspecified+no_connect"))
    )
    (net (code "69") (name "unconnected-(U6-IO14-Pad13)") (class "Default")
      (node (ref "U6") (pin "13") (pinfunction "IO14_13") (pintype "unspecified+no_connect"))
    )
    (net (code "70") (name "unconnected-(U6-IO15-Pad23)") (class "Default")
      (node (ref "U6") (pin "23") (pinfunction "IO15_23") (pintype "unspecified+no_connect"))
    )
    (net (code "71") (name "unconnected-(U6-IO17-Pad28)") (class "Default")
      (node (ref "U6") (pin "28") (pinfunction "IO17_28") (pintype "unspecified+no_connect"))
    )
    (net (code "72") (name "unconnected-(U6-IO18-Pad30)") (class "Default")
      (node (ref "U6") (pin "30") (pinfunction "IO18_30") (pintype "unspecified+no_connect"))
    )
    (net (code "73") (name "unconnected-(U6-IO19-Pad31)") (class "Default")
      (node (ref "U6") (pin "31") (pinfunction "IO19_31") (pintype "unspecified+no_connect"))
    )
    (net (code "74") (name "unconnected-(U6-IO21-Pad33)") (class "Default")
      (node (ref "U6") (pin "33") (pinfunction "IO21_33") (pintype "unspecified+no_connect"))
    )
    (net (code "75") (name "unconnected-(U6-IO23-Pad37)") (class "Default")
      (node (ref "U6") (pin "37") (pinfunction "IO23_37") (pintype "unspecified+no_connect"))
    )
    (net (code "76") (name "unconnected-(U6-IO27-Pad12)") (class "Default")
      (node (ref "U6") (pin "12") (pinfunction "IO27_12") (pintype "unspecified+no_connect"))
    )
    (net (code "77") (name "unconnected-(U6-IO32-Pad8)") (class "Default")
      (node (ref "U6") (pin "8") (pinfunction "IO32_8") (pintype "unspecified+no_connect"))
    )
    (net (code "78") (name "unconnected-(U6-IO33-Pad9)") (class "Default")
      (node (ref "U6") (pin "9") (pinfunction "IO33_9") (pintype "unspecified+no_connect"))
    )
    (net (code "79") (name "unconnected-(U6-IO34-Pad6)") (class "Default")
      (node (ref "U6") (pin "6") (pinfunction "IO34_6") (pintype "unspecified+no_connect"))
    )
    (net (code "80") (name "unconnected-(U6-IO35-Pad7)") (class "Default")
      (node (ref "U6") (pin "7") (pinfunction "IO35_7") (pintype "unspecified+no_connect"))
    )
    (net (code "81") (name "unconnected-(U6-NC-Pad17)") (class "Default")
      (node (ref "U6") (pin "17") (pinfunction "NC_17") (pintype "unspecified+no_connect"))
    )
    (net (code "82") (name "unconnected-(U6-NC-Pad18)") (class "Default")
      (node (ref "U6") (pin "18") (pinfunction "NC_18") (pintype "unspecified+no_connect"))
    )
    (net (code "83") (name "unconnected-(U6-NC-Pad19)") (class "Default")
      (node (ref "U6") (pin "19") (pinfunction "NC_19") (pintype "unspecified+no_connect"))
    )
    (net (code "84") (name "unconnected-(U6-NC-Pad20)") (class "Default")
      (node (ref "U6") (pin "20") (pinfunction "NC_20") (pintype "unspecified+no_connect"))
    )
    (net (code "85") (name "unconnected-(U6-NC-Pad21)") (class "Default")
      (node (ref "U6") (pin "21") (pinfunction "NC_21") (pintype "unspecified+no_connect"))
    )
    (net (code "86") (name "unconnected-(U6-NC-Pad22)") (class "Default")
      (node (ref "U6") (pin "22") (pinfunction "NC_22") (pintype "unspecified+no_connect"))
    )
    (net (code "87") (name "unconnected-(U6-NC-Pad32)") (class "Default")
      (node (ref "U6") (pin "32") (pinfunction "NC_32") (pintype "unspecified+no_connect"))
    )
    (net (code "88") (name "unconnected-(U6-SENSOR_VN-Pad5)") (class "Default")
      (node (ref "U6") (pin "5") (pinfunction "SENSOR_VN_5") (pintype "unspecified+no_connect"))
    )
    (net (code "89") (name "unconnected-(U6-SENSOR_VP-Pad4)") (class "Default")
      (node (ref "U6") (pin "4") (pinfunction "SENSOR_VP_4") (pintype "unspecified+no_connect"))
    )
    (net (code "90") (name "unconnected-(U7-SCK-Pad12)") (class "Default")
      (node (ref "U7") (pin "12") (pinfunction "SCK_12") (pintype "input+no_connect"))
    )
    (net (code "91") (name "unconnected-(U8-MUTE#-Pad5)") (class "Default")
      (node (ref "U8") (pin "5") (pinfunction "MUTE#_5") (pintype "unspecified+no_connect"))
    )
    (net (code "92") (name "unconnected-(USBC1-SBU1-PadA8)") (class "Default")
      (node (ref "USBC1") (pin "A8") (pinfunction "SBU1_A8") (pintype "unspecified+no_connect"))
    )
    (net (code "93") (name "unconnected-(USBC1-SBU2-PadB8)") (class "Default")
      (node (ref "USBC1") (pin "B8") (pinfunction "SBU2_B8") (pintype "unspecified+no_connect"))
    )
  )
)
